# Controller.net
KiCad netlist of a schematic drawn in EAGLE
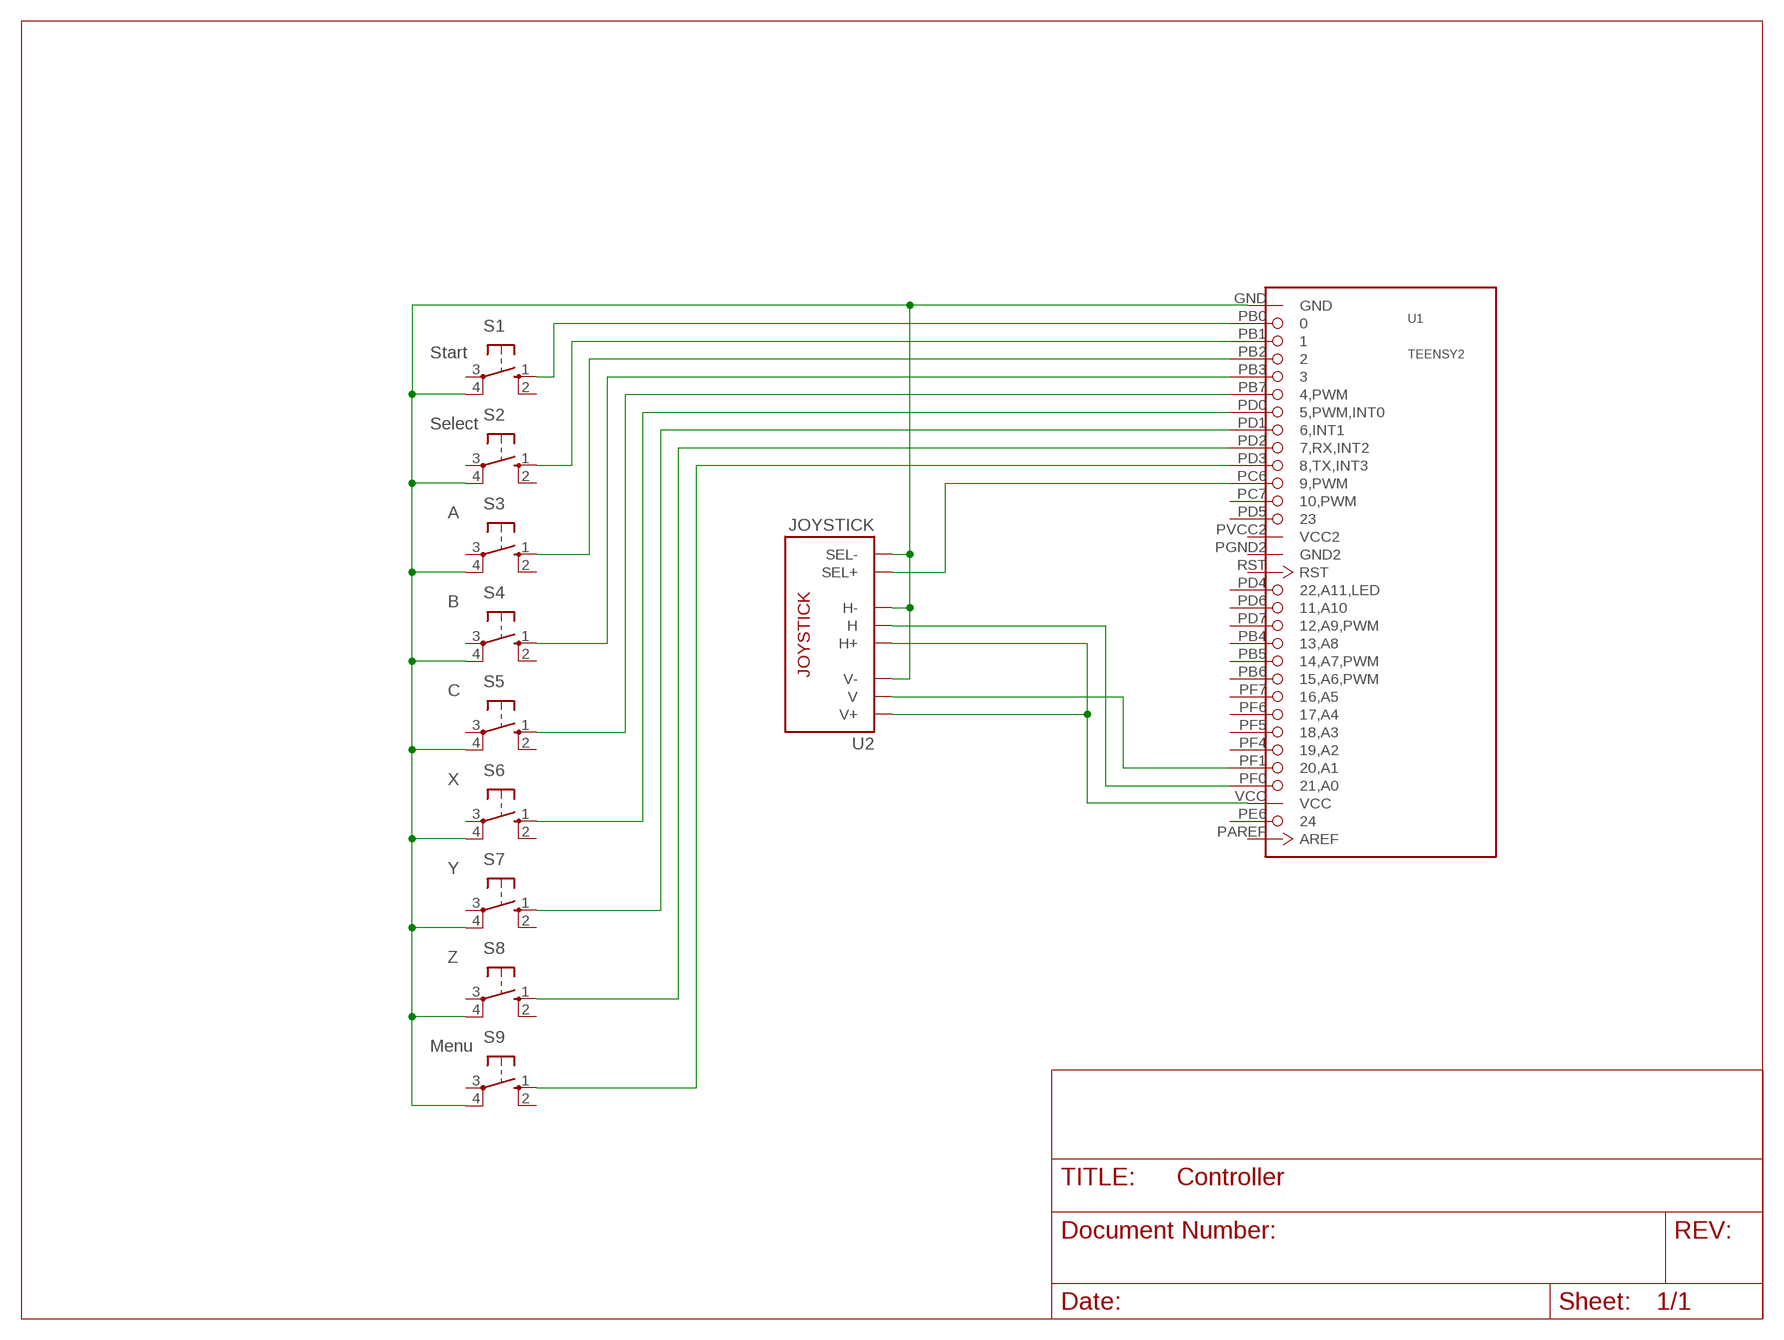
[diagram p0: schematic, sheet 1]

(export (version "E")
  (design (tool "Eeschema 10.0.6"))
  (components
    (comp (ref "S1")
      (value "10-XX")
      (footprint "eagle-import:B3F-10XX")
      (fields (field (name "MPN") "B3F-1000"))
      (libsource (lib "eagle-import") (part "10-XX"))
    )
    (comp (ref "S2")
      (value "10-XX")
      (footprint "eagle-import:B3F-10XX")
      (fields (field (name "MPN") "B3F-1000"))
      (libsource (lib "eagle-import") (part "10-XX"))
    )
    (comp (ref "S3")
      (value "10-XX")
      (footprint "eagle-import:B3F-10XX")
      (fields (field (name "MPN") "B3F-1000"))
      (libsource (lib "eagle-import") (part "10-XX"))
    )
    (comp (ref "S4")
      (value "10-XX")
      (footprint "eagle-import:B3F-10XX")
      (fields (field (name "MPN") "B3F-1000"))
      (libsource (lib "eagle-import") (part "10-XX"))
    )
    (comp (ref "S5")
      (value "10-XX")
      (footprint "eagle-import:B3F-10XX")
      (fields (field (name "MPN") "B3F-1000"))
      (libsource (lib "eagle-import") (part "10-XX"))
    )
    (comp (ref "S6")
      (value "10-XX")
      (footprint "eagle-import:B3F-10XX")
      (fields (field (name "MPN") "B3F-1000"))
      (libsource (lib "eagle-import") (part "10-XX"))
    )
    (comp (ref "S7")
      (value "10-XX")
      (footprint "eagle-import:B3F-10XX")
      (fields (field (name "MPN") "B3F-1000"))
      (libsource (lib "eagle-import") (part "10-XX"))
    )
    (comp (ref "S8")
      (value "10-XX")
      (footprint "eagle-import:B3F-10XX")
      (fields (field (name "MPN") "B3F-1000"))
      (libsource (lib "eagle-import") (part "10-XX"))
    )
    (comp (ref "S9")
      (value "10-XX")
      (footprint "eagle-import:B3F-10XX")
      (fields (field (name "MPN") "B3F-1000"))
      (libsource (lib "eagle-import") (part "10-XX"))
    )
    (comp (ref "U1")
      (value "TEENSY2")
      (footprint "eagle-import:TEENSY2")
      (libsource (lib "eagle-import") (part "TEENSY2-ARDUINO"))
    )
    (comp (ref "U2")
      (value "JOYSTICK")
      (footprint "eagle-import:JOYSTICK")
      (libsource (lib "eagle-import") (part "JOYSTICKPTH"))
    )
  )
  (nets
    (net (code "1") (name "/GND2") (class "Default")
      (node (ref "U1") (pin "PGND2") (pinfunction "GND2_PGND2") (pintype "power_in"))
    )
    (net (code "2") (name "/VCC2") (class "Default")
      (node (ref "U1") (pin "PVCC2") (pinfunction "VCC2_PVCC2") (pintype "power_in"))
    )
    (net (code "3") (name "Net-(S1-P1)") (class "Default")
      (node (ref "S1") (pin "4") (pinfunction "P1_4") (pintype "passive"))
      (node (ref "S2") (pin "4") (pinfunction "P1_4") (pintype "passive"))
      (node (ref "S3") (pin "4") (pinfunction "P1_4") (pintype "passive"))
      (node (ref "S4") (pin "4") (pinfunction "P1_4") (pintype "passive"))
      (node (ref "S5") (pin "4") (pinfunction "P1_4") (pintype "passive"))
      (node (ref "S6") (pin "4") (pinfunction "P1_4") (pintype "passive"))
      (node (ref "S7") (pin "4") (pinfunction "P1_4") (pintype "passive"))
      (node (ref "S8") (pin "4") (pinfunction "P1_4") (pintype "passive"))
      (node (ref "S9") (pin "4") (pinfunction "P1_4") (pintype "passive"))
      (node (ref "U1") (pin "GND") (pinfunction "GND_GND") (pintype "power_in"))
      (node (ref "U2") (pin "B2A") (pinfunction "SEL-_B2A") (pintype "bidirectional"))
      (node (ref "U2") (pin "H3") (pinfunction "H-_H3") (pintype "bidirectional"))
      (node (ref "U2") (pin "V3") (pinfunction "V-_V3") (pintype "bidirectional"))
    )
    (net (code "4") (name "Net-(S1-S)") (class "Default")
      (node (ref "S1") (pin "1") (pinfunction "S_1") (pintype "passive"))
      (node (ref "U1") (pin "PB0") (pinfunction "0_PB0") (pintype "bidirectional"))
    )
    (net (code "5") (name "Net-(S2-S)") (class "Default")
      (node (ref "S2") (pin "1") (pinfunction "S_1") (pintype "passive"))
      (node (ref "U1") (pin "PB1") (pinfunction "1_PB1") (pintype "bidirectional"))
    )
    (net (code "6") (name "Net-(S3-S)") (class "Default")
      (node (ref "S3") (pin "1") (pinfunction "S_1") (pintype "passive"))
      (node (ref "U1") (pin "PB2") (pinfunction "2_PB2") (pintype "bidirectional"))
    )
    (net (code "7") (name "Net-(S4-S)") (class "Default")
      (node (ref "S4") (pin "1") (pinfunction "S_1") (pintype "passive"))
      (node (ref "U1") (pin "PB3") (pinfunction "3_PB3") (pintype "bidirectional"))
    )
    (net (code "8") (name "Net-(S5-S)") (class "Default")
      (node (ref "S5") (pin "1") (pinfunction "S_1") (pintype "passive"))
      (node (ref "U1") (pin "PB7") (pinfunction "4,PWM_PB7") (pintype "bidirectional"))
    )
    (net (code "9") (name "Net-(S6-S)") (class "Default")
      (node (ref "S6") (pin "1") (pinfunction "S_1") (pintype "passive"))
      (node (ref "U1") (pin "PD0") (pinfunction "5,PWM,INT0_PD0") (pintype "bidirectional"))
    )
    (net (code "10") (name "Net-(S7-S)") (class "Default")
      (node (ref "S7") (pin "1") (pinfunction "S_1") (pintype "passive"))
      (node (ref "U1") (pin "PD1") (pinfunction "6,INT1_PD1") (pintype "bidirectional"))
    )
    (net (code "11") (name "Net-(S8-S)") (class "Default")
      (node (ref "S8") (pin "1") (pinfunction "S_1") (pintype "passive"))
      (node (ref "U1") (pin "PD2") (pinfunction "7,RX,INT2_PD2") (pintype "bidirectional"))
    )
    (net (code "12") (name "Net-(S9-S)") (class "Default")
      (node (ref "S9") (pin "1") (pinfunction "S_1") (pintype "passive"))
      (node (ref "U1") (pin "PD3") (pinfunction "8,TX,INT3_PD3") (pintype "bidirectional"))
    )
    (net (code "13") (name "Net-(U1-9,PWM)") (class "Default")
      (node (ref "U1") (pin "PC6") (pinfunction "9,PWM_PC6") (pintype "bidirectional"))
      (node (ref "U2") (pin "B1A") (pinfunction "SEL+_B1A") (pintype "bidirectional"))
    )
    (net (code "14") (name "Net-(U1-20,A1)") (class "Default")
      (node (ref "U1") (pin "PF1") (pinfunction "20,A1_PF1") (pintype "bidirectional"))
      (node (ref "U2") (pin "V2") (pinfunction "V_V2") (pintype "bidirectional"))
    )
    (net (code "15") (name "Net-(U1-21,A0)") (class "Default")
      (node (ref "U1") (pin "PF0") (pinfunction "21,A0_PF0") (pintype "bidirectional"))
      (node (ref "U2") (pin "H2") (pinfunction "H_H2") (pintype "bidirectional"))
    )
    (net (code "16") (name "Net-(U2-H+)") (class "Default")
      (node (ref "U1") (pin "VCC") (pinfunction "VCC_VCC") (pintype "power_in"))
      (node (ref "U2") (pin "H1") (pinfunction "H+_H1") (pintype "bidirectional"))
      (node (ref "U2") (pin "V1") (pinfunction "V+_V1") (pintype "bidirectional"))
    )
    (net (code "17") (name "unconnected-(S1-P-Pad3)") (class "Default")
      (node (ref "S1") (pin "3") (pinfunction "P_3") (pintype "passive"))
    )
    (net (code "18") (name "unconnected-(S1-S1-Pad2)") (class "Default")
      (node (ref "S1") (pin "2") (pinfunction "S1_2") (pintype "passive"))
    )
    (net (code "19") (name "unconnected-(S2-P-Pad3)") (class "Default")
      (node (ref "S2") (pin "3") (pinfunction "P_3") (pintype "passive"))
    )
    (net (code "20") (name "unconnected-(S2-S1-Pad2)") (class "Default")
      (node (ref "S2") (pin "2") (pinfunction "S1_2") (pintype "passive"))
    )
    (net (code "21") (name "unconnected-(S3-P-Pad3)") (class "Default")
      (node (ref "S3") (pin "3") (pinfunction "P_3") (pintype "passive"))
    )
    (net (code "22") (name "unconnected-(S3-S1-Pad2)") (class "Default")
      (node (ref "S3") (pin "2") (pinfunction "S1_2") (pintype "passive"))
    )
    (net (code "23") (name "unconnected-(S4-P-Pad3)") (class "Default")
      (node (ref "S4") (pin "3") (pinfunction "P_3") (pintype "passive"))
    )
    (net (code "24") (name "unconnected-(S4-S1-Pad2)") (class "Default")
      (node (ref "S4") (pin "2") (pinfunction "S1_2") (pintype "passive"))
    )
    (net (code "25") (name "unconnected-(S5-P-Pad3)") (class "Default")
      (node (ref "S5") (pin "3") (pinfunction "P_3") (pintype "passive"))
    )
    (net (code "26") (name "unconnected-(S5-S1-Pad2)") (class "Default")
      (node (ref "S5") (pin "2") (pinfunction "S1_2") (pintype "passive"))
    )
    (net (code "27") (name "unconnected-(S6-P-Pad3)") (class "Default")
      (node (ref "S6") (pin "3") (pinfunction "P_3") (pintype "passive"))
    )
    (net (code "28") (name "unconnected-(S6-S1-Pad2)") (class "Default")
      (node (ref "S6") (pin "2") (pinfunction "S1_2") (pintype "passive"))
    )
    (net (code "29") (name "unconnected-(S7-P-Pad3)") (class "Default")
      (node (ref "S7") (pin "3") (pinfunction "P_3") (pintype "passive"))
    )
    (net (code "30") (name "unconnected-(S7-S1-Pad2)") (class "Default")
      (node (ref "S7") (pin "2") (pinfunction "S1_2") (pintype "passive"))
    )
    (net (code "31") (name "unconnected-(S8-P-Pad3)") (class "Default")
      (node (ref "S8") (pin "3") (pinfunction "P_3") (pintype "passive"))
    )
    (net (code "32") (name "unconnected-(S8-S1-Pad2)") (class "Default")
      (node (ref "S8") (pin "2") (pinfunction "S1_2") (pintype "passive"))
    )
    (net (code "33") (name "unconnected-(S9-P-Pad3)") (class "Default")
      (node (ref "S9") (pin "3") (pinfunction "P_3") (pintype "passive"))
    )
    (net (code "34") (name "unconnected-(S9-S1-Pad2)") (class "Default")
      (node (ref "S9") (pin "2") (pinfunction "S1_2") (pintype "passive"))
    )
    (net (code "35") (name "unconnected-(U1-10,PWM-PadPC7)") (class "Default")
      (node (ref "U1") (pin "PC7") (pinfunction "10,PWM_PC7") (pintype "bidirectional"))
    )
    (net (code "36") (name "unconnected-(U1-11,A10-PadPD6)") (class "Default")
      (node (ref "U1") (pin "PD6") (pinfunction "11,A10_PD6") (pintype "bidirectional"))
    )
    (net (code "37") (name "unconnected-(U1-12,A9,PWM-PadPD7)") (class "Default")
      (node (ref "U1") (pin "PD7") (pinfunction "12,A9,PWM_PD7") (pintype "bidirectional"))
    )
    (net (code "38") (name "unconnected-(U1-13,A8-PadPB4)") (class "Default")
      (node (ref "U1") (pin "PB4") (pinfunction "13,A8_PB4") (pintype "bidirectional"))
    )
    (net (code "39") (name "unconnected-(U1-14,A7,PWM-PadPB5)") (class "Default")
      (node (ref "U1") (pin "PB5") (pinfunction "14,A7,PWM_PB5") (pintype "bidirectional"))
    )
    (net (code "40") (name "unconnected-(U1-15,A6,PWM-PadPB6)") (class "Default")
      (node (ref "U1") (pin "PB6") (pinfunction "15,A6,PWM_PB6") (pintype "bidirectional"))
    )
    (net (code "41") (name "unconnected-(U1-16,A5-PadPF7)") (class "Default")
      (node (ref "U1") (pin "PF7") (pinfunction "16,A5_PF7") (pintype "bidirectional"))
    )
    (net (code "42") (name "unconnected-(U1-17,A4-PadPF6)") (class "Default")
      (node (ref "U1") (pin "PF6") (pinfunction "17,A4_PF6") (pintype "bidirectional"))
    )
    (net (code "43") (name "unconnected-(U1-18,A3-PadPF5)") (class "Default")
      (node (ref "U1") (pin "PF5") (pinfunction "18,A3_PF5") (pintype "bidirectional"))
    )
    (net (code "44") (name "unconnected-(U1-19,A2-PadPF4)") (class "Default")
      (node (ref "U1") (pin "PF4") (pinfunction "19,A2_PF4") (pintype "bidirectional"))
    )
    (net (code "45") (name "unconnected-(U1-22,A11,LED-PadPD4)") (class "Default")
      (node (ref "U1") (pin "PD4") (pinfunction "22,A11,LED_PD4") (pintype "bidirectional"))
    )
    (net (code "46") (name "unconnected-(U1-23-PadPD5)") (class "Default")
      (node (ref "U1") (pin "PD5") (pinfunction "23_PD5") (pintype "bidirectional"))
    )
    (net (code "47") (name "unconnected-(U1-24-PadPE6)") (class "Default")
      (node (ref "U1") (pin "PE6") (pinfunction "24_PE6") (pintype "bidirectional"))
    )
    (net (code "48") (name "unconnected-(U1-AREF-PadPAREF)") (class "Default")
      (node (ref "U1") (pin "PAREF") (pinfunction "AREF_PAREF") (pintype "input"))
    )
    (net (code "49") (name "unconnected-(U1-PadRST)") (class "Default")
      (node (ref "U1") (pin "RST") (pinfunction "RST_RST") (pintype "input"))
    )
  )
)
